# telemetry-b1.net
KiCad netlist of a schematic drawn in EAGLE
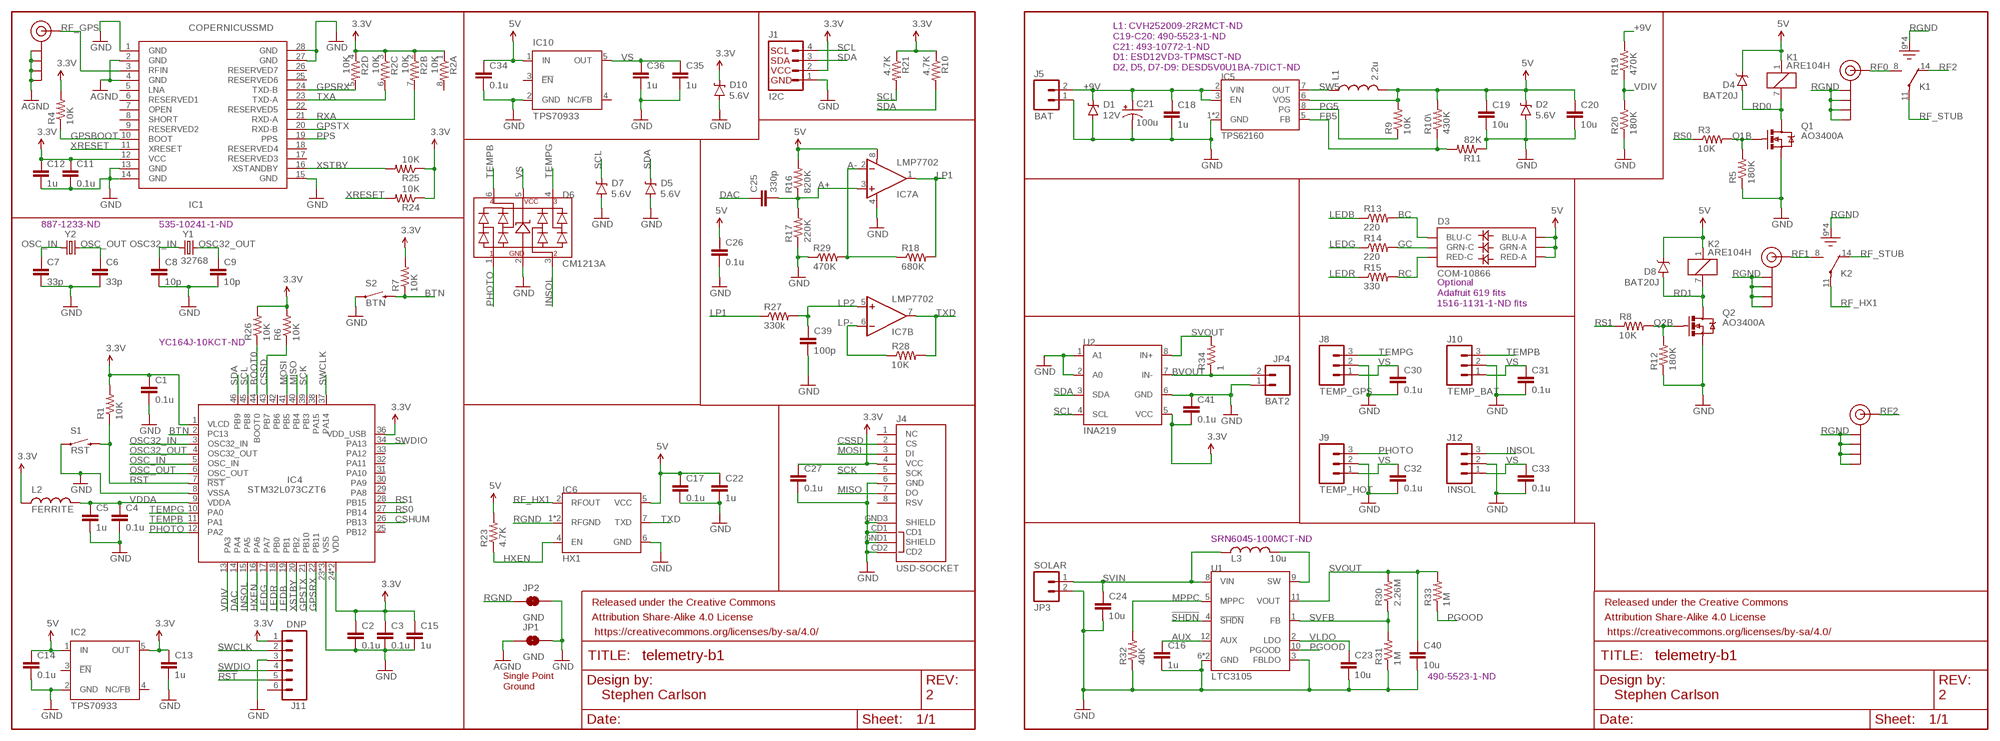
[diagram p0: schematic, sheet 1]

(export (version "E")
  (design (tool "Eeschema 10.0.6"))
  (components
    (comp (ref "C1")
      (value "0.1u")
      (footprint "eagle-import:0805")
      (libsource (lib "eagle-import") (part "CAP0805"))
    )
    (comp (ref "C2")
      (value "0.1u")
      (footprint "eagle-import:0805")
      (libsource (lib "eagle-import") (part "CAP0805"))
    )
    (comp (ref "C3")
      (value "0.1u")
      (footprint "eagle-import:0805")
      (libsource (lib "eagle-import") (part "CAP0805"))
    )
    (comp (ref "C4")
      (value "0.1u")
      (footprint "eagle-import:0805")
      (libsource (lib "eagle-import") (part "CAP0805"))
    )
    (comp (ref "C5")
      (value "1u")
      (footprint "eagle-import:0805")
      (libsource (lib "eagle-import") (part "CAP0805"))
    )
    (comp (ref "C6")
      (value "33p")
      (footprint "eagle-import:0805")
      (libsource (lib "eagle-import") (part "CAP0805"))
    )
    (comp (ref "C7")
      (value "33p")
      (footprint "eagle-import:0805")
      (libsource (lib "eagle-import") (part "CAP0805"))
    )
    (comp (ref "C8")
      (value "10p")
      (footprint "eagle-import:0805")
      (libsource (lib "eagle-import") (part "CAP0805"))
    )
    (comp (ref "C9")
      (value "10p")
      (footprint "eagle-import:0805")
      (libsource (lib "eagle-import") (part "CAP0805"))
    )
    (comp (ref "C11")
      (value "0.1u")
      (footprint "eagle-import:0805")
      (libsource (lib "eagle-import") (part "CAP0805"))
    )
    (comp (ref "C12")
      (value "1u")
      (footprint "eagle-import:0805")
      (libsource (lib "eagle-import") (part "CAP0805"))
    )
    (comp (ref "C13")
      (value "1u")
      (footprint "eagle-import:0805")
      (libsource (lib "eagle-import") (part "CAP0805"))
    )
    (comp (ref "C14")
      (value "0.1u")
      (footprint "eagle-import:0805")
      (libsource (lib "eagle-import") (part "CAP0805"))
    )
    (comp (ref "C15")
      (value "1u")
      (footprint "eagle-import:0805")
      (libsource (lib "eagle-import") (part "CAP0805"))
    )
    (comp (ref "C16")
      (value "1u")
      (footprint "eagle-import:0805")
      (libsource (lib "eagle-import") (part "CAP0805"))
    )
    (comp (ref "C17")
      (value "0.1u")
      (footprint "eagle-import:0805")
      (libsource (lib "eagle-import") (part "CAP0805"))
    )
    (comp (ref "C18")
      (value "1u")
      (footprint "eagle-import:0805")
      (libsource (lib "eagle-import") (part "CAP0805"))
    )
    (comp (ref "C19")
      (value "10u")
      (footprint "eagle-import:0805")
      (libsource (lib "eagle-import") (part "CAP0805"))
    )
    (comp (ref "C20")
      (value "10u")
      (footprint "eagle-import:0805")
      (libsource (lib "eagle-import") (part "CAP0805"))
    )
    (comp (ref "C21")
      (value "100u")
      (footprint "eagle-import:CPOL-RADIAL-10UF-25V")
      (libsource (lib "eagle-import") (part "CAP_POLPTH2"))
    )
    (comp (ref "C22")
      (value "1u")
      (footprint "eagle-import:0805")
      (libsource (lib "eagle-import") (part "CAP0805"))
    )
    (comp (ref "C23")
      (value "10u")
      (footprint "eagle-import:0805")
      (libsource (lib "eagle-import") (part "CAP0805"))
    )
    (comp (ref "C24")
      (value "10u")
      (footprint "eagle-import:0805")
      (libsource (lib "eagle-import") (part "CAP0805"))
    )
    (comp (ref "C25")
      (value "330p")
      (footprint "eagle-import:0805")
      (libsource (lib "eagle-import") (part "CAP0805"))
    )
    (comp (ref "C26")
      (value "0.1u")
      (footprint "eagle-import:0805")
      (libsource (lib "eagle-import") (part "CAP0805"))
    )
    (comp (ref "C27")
      (value "0.1u")
      (footprint "eagle-import:0805")
      (libsource (lib "eagle-import") (part "CAP0805"))
    )
    (comp (ref "C30")
      (value "0.1u")
      (footprint "eagle-import:0805")
      (libsource (lib "eagle-import") (part "CAP0805"))
    )
    (comp (ref "C31")
      (value "0.1u")
      (footprint "eagle-import:0805")
      (libsource (lib "eagle-import") (part "CAP0805"))
    )
    (comp (ref "C32")
      (value "0.1u")
      (footprint "eagle-import:0805")
      (libsource (lib "eagle-import") (part "CAP0805"))
    )
    (comp (ref "C33")
      (value "0.1u")
      (footprint "eagle-import:0805")
      (libsource (lib "eagle-import") (part "CAP0805"))
    )
    (comp (ref "C34")
      (value "0.1u")
      (footprint "eagle-import:0805")
      (libsource (lib "eagle-import") (part "CAP0805"))
    )
    (comp (ref "C35")
      (value "1u")
      (footprint "eagle-import:0805")
      (libsource (lib "eagle-import") (part "CAP0805"))
    )
    (comp (ref "C36")
      (value "1u")
      (footprint "eagle-import:0805")
      (libsource (lib "eagle-import") (part "CAP0805"))
    )
    (comp (ref "C39")
      (value "100p")
      (footprint "eagle-import:0805")
      (libsource (lib "eagle-import") (part "CAP0805"))
    )
    (comp (ref "C40")
      (value "10u")
      (footprint "eagle-import:0805")
      (libsource (lib "eagle-import") (part "CAP0805"))
    )
    (comp (ref "C41")
      (value "0.1u")
      (footprint "eagle-import:0805")
      (libsource (lib "eagle-import") (part "CAP0805"))
    )
    (comp (ref "D1")
      (value "12V")
      (footprint "eagle-import:SOD-323")
      (libsource (lib "eagle-import") (part "DIODE-ZENER5.6V"))
    )
    (comp (ref "D2")
      (value "5.6V")
      (footprint "eagle-import:SOD-323")
      (libsource (lib "eagle-import") (part "DIODE-ZENER5.6V"))
    )
    (comp (ref "D3")
      (value "COM-10866")
      (footprint "eagle-import:LED-TRICOLOR-5050")
      (libsource (lib "eagle-import") (part "LED-TRICOLOR-5050NO_IC"))
    )
    (comp (ref "D4")
      (value "BAT20J")
      (footprint "eagle-import:SOD-323")
      (libsource (lib "eagle-import") (part "DIODE-SCHOTTKY-BAT20J"))
    )
    (comp (ref "D5")
      (value "5.6V")
      (footprint "eagle-import:SOD-323")
      (libsource (lib "eagle-import") (part "DIODE-ZENER5.6V"))
    )
    (comp (ref "D6")
      (value "CM1213A")
      (footprint "eagle-import:SC70-6L")
      (libsource (lib "eagle-import") (part "CM1213A"))
    )
    (comp (ref "D7")
      (value "5.6V")
      (footprint "eagle-import:SOD-323")
      (libsource (lib "eagle-import") (part "DIODE-ZENER5.6V"))
    )
    (comp (ref "D8")
      (value "BAT20J")
      (footprint "eagle-import:SOD-323")
      (libsource (lib "eagle-import") (part "DIODE-SCHOTTKY-BAT20J"))
    )
    (comp (ref "D10")
      (value "5.6V")
      (footprint "eagle-import:SOD-323")
      (libsource (lib "eagle-import") (part "DIODE-ZENER5.6V"))
    )
    (comp (ref "FRAME1")
      (value "FRAME-LETTERNO_PACKAGE")
      (footprint "eagle-import:DUMMY")
      (fields (field (name "DESIGNER") "Nobody"))
      (libsource (lib "eagle-import") (part "FRAME-LETTERNO_PACKAGE"))
    )
    (comp (ref "FRAME2")
      (value "FRAME-LETTERNO_PACKAGE")
      (footprint "eagle-import:DUMMY")
      (fields (field (name "DESIGNER") "Nobody"))
      (libsource (lib "eagle-import") (part "FRAME-LETTERNO_PACKAGE"))
    )
    (comp (ref "IC1")
      (value "COPERNICUSSMD")
      (footprint "eagle-import:COPERNICUS")
      (libsource (lib "eagle-import") (part "COPERNICUSSMD"))
    )
    (comp (ref "IC2")
      (value "TPS70933")
      (footprint "eagle-import:SOT23-DBV")
      (fields (field (name "MF") "TEXAS INSTRUMENTS") (field (name "MPN") "TPS77033DBVT"))
      (libsource (lib "eagle-import") (part "TPS77033"))
    )
    (comp (ref "IC4")
      (value "STM32L073CZT6")
      (footprint "eagle-import:TQFP48")
      (libsource (lib "eagle-import") (part "STM32L07C"))
    )
    (comp (ref "IC5")
      (value "TPS62160")
      (footprint "eagle-import:MSOP8")
      (libsource (lib "eagle-import") (part "TPS62160"))
    )
    (comp (ref "IC6")
      (value "HX1")
      (footprint "eagle-import:HX1")
      (libsource (lib "eagle-import") (part "HX1"))
    )
    (comp (ref "IC7")
      (value "LMP7702")
      (footprint "eagle-import:SO08")
      (libsource (lib "eagle-import") (part "OPAMP-DUALU"))
    )
    (comp (ref "IC10")
      (value "TPS70933")
      (footprint "eagle-import:SOT23-DBV")
      (fields (field (name "MF") "TEXAS INSTRUMENTS") (field (name "MPN") "TPS77033DBVT"))
      (libsource (lib "eagle-import") (part "TPS77033"))
    )
    (comp (ref "J1")
      (value "I2C")
      (footprint "eagle-import:1X04_NO_SILK")
      (libsource (lib "eagle-import") (part "I2C_STANDARD_NO_SILK"))
    )
    (comp (ref "J3")
      (value "SMA_EDGE")
      (footprint "eagle-import:SMA-EDGE")
      (libsource (lib "eagle-import") (part "SMA_EDGE"))
    )
    (comp (ref "J4")
      (value "USD-SOCKET")
      (footprint "eagle-import:MICROSD_1_1")
      (libsource (lib "eagle-import") (part "USD-SOCKET"))
    )
    (comp (ref "J5")
      (value "BAT")
      (footprint "eagle-import:1X02")
      (libsource (lib "eagle-import") (part "M02PTH"))
    )
    (comp (ref "J6")
      (value "SMA_EDGE")
      (footprint "eagle-import:SMA-EDGE")
      (libsource (lib "eagle-import") (part "SMA_EDGE"))
    )
    (comp (ref "J7")
      (value "SMA_EDGE")
      (footprint "eagle-import:SMA-EDGE")
      (libsource (lib "eagle-import") (part "SMA_EDGE"))
    )
    (comp (ref "J8")
      (value "TEMP_GPS")
      (footprint "eagle-import:JST-3-PTH")
      (libsource (lib "eagle-import") (part "M03JST-PTH"))
    )
    (comp (ref "J9")
      (value "TEMP_HOT")
      (footprint "eagle-import:JST-3-PTH")
      (libsource (lib "eagle-import") (part "M03JST-PTH"))
    )
    (comp (ref "J10")
      (value "TEMP_BAT")
      (footprint "eagle-import:JST-3-PTH")
      (libsource (lib "eagle-import") (part "M03JST-PTH"))
    )
    (comp (ref "J11")
      (value "DNP")
      (footprint "eagle-import:1X06_LOCK")
      (libsource (lib "eagle-import") (part "M06LOCK"))
    )
    (comp (ref "J12")
      (value "INSOL")
      (footprint "eagle-import:JST-3-PTH")
      (libsource (lib "eagle-import") (part "M03JST-PTH"))
    )
    (comp (ref "J13")
      (value "SMA_EDGE")
      (footprint "eagle-import:SMA-EDGE")
      (libsource (lib "eagle-import") (part "SMA_EDGE"))
    )
    (comp (ref "JP1")
      (value "GND")
      (footprint "eagle-import:PAD-JUMPER-2-NC_BY_TRACE_YES_SILK")
      (libsource (lib "eagle-import") (part "JUMPER-PAD-2-NC_BY_TRACE"))
    )
    (comp (ref "JP2")
      (value "GND")
      (footprint "eagle-import:PAD-JUMPER-2-NC_BY_TRACE_YES_SILK")
      (libsource (lib "eagle-import") (part "JUMPER-PAD-2-NC_BY_TRACE"))
    )
    (comp (ref "JP3")
      (value "SOLAR")
      (footprint "eagle-import:1X02")
      (libsource (lib "eagle-import") (part "M02PTH"))
    )
    (comp (ref "JP4")
      (value "BAT2")
      (footprint "eagle-import:1X02")
      (libsource (lib "eagle-import") (part "M02PTH"))
    )
    (comp (ref "K1")
      (value "ARE104H")
      (footprint "eagle-import:RFDIL14")
      (libsource (lib "eagle-import") (part "RF_RELAY"))
    )
    (comp (ref "K2")
      (value "ARE104H")
      (footprint "eagle-import:RFDIL14")
      (libsource (lib "eagle-import") (part "RF_RELAY"))
    )
    (comp (ref "L1")
      (value "2.2u")
      (footprint "eagle-import:1008")
      (libsource (lib "eagle-import") (part "INDUCTOR1008"))
    )
    (comp (ref "L2")
      (value "FERRITE")
      (footprint "eagle-import:1206")
      (libsource (lib "eagle-import") (part "INDUCTOR1206"))
    )
    (comp (ref "L3")
      (value "10u")
      (footprint "eagle-import:SRN6045")
      (libsource (lib "eagle-import") (part "INDUCTORBOURNS_SRN6045"))
    )
    (comp (ref "Q1")
      (value "AO3400A")
      (footprint "eagle-import:SOT23-3")
      (libsource (lib "eagle-import") (part "MOSFET-NCHANNELAO3404A"))
    )
    (comp (ref "Q2")
      (value "AO3400A")
      (footprint "eagle-import:SOT23-3")
      (libsource (lib "eagle-import") (part "MOSFET-NCHANNELAO3404A"))
    )
    (comp (ref "R1")
      (value "10K")
      (footprint "eagle-import:0805")
      (libsource (lib "eagle-import") (part "RESISTOR0805-RES"))
    )
    (comp (ref "R2")
      (value "10K")
      (footprint "eagle-import:0603-ARV")
      (libsource (lib "eagle-import") (part "RESISTOR-ARRAY0603-ARV"))
    )
    (comp (ref "R3")
      (value "10K")
      (footprint "eagle-import:0805")
      (libsource (lib "eagle-import") (part "RESISTOR0805-RES"))
    )
    (comp (ref "R4")
      (value "10K")
      (footprint "eagle-import:0805")
      (libsource (lib "eagle-import") (part "RESISTOR0805-RES"))
    )
    (comp (ref "R5")
      (value "180K")
      (footprint "eagle-import:0805")
      (libsource (lib "eagle-import") (part "RESISTOR0805-RES"))
    )
    (comp (ref "R6")
      (value "10K")
      (footprint "eagle-import:0805")
      (libsource (lib "eagle-import") (part "RESISTOR0805-RES"))
    )
    (comp (ref "R7")
      (value "10K")
      (footprint "eagle-import:0805")
      (libsource (lib "eagle-import") (part "RESISTOR0805-RES"))
    )
    (comp (ref "R8")
      (value "10K")
      (footprint "eagle-import:0805")
      (libsource (lib "eagle-import") (part "RESISTOR0805-RES"))
    )
    (comp (ref "R9")
      (value "10K")
      (footprint "eagle-import:0805")
      (libsource (lib "eagle-import") (part "RESISTOR0805-RES"))
    )
    (comp (ref "R10")
      (value "4.7K")
      (footprint "eagle-import:0805")
      (libsource (lib "eagle-import") (part "RESISTOR0805-RES"))
    )
    (comp (ref "R10\\")
      (value "430K")
      (footprint "eagle-import:0805")
      (libsource (lib "eagle-import") (part "RESISTOR0805-RES"))
    )
    (comp (ref "R11")
      (value "82K")
      (footprint "eagle-import:0805")
      (libsource (lib "eagle-import") (part "RESISTOR0805-RES"))
    )
    (comp (ref "R12")
      (value "180K")
      (footprint "eagle-import:0805")
      (libsource (lib "eagle-import") (part "RESISTOR0805-RES"))
    )
    (comp (ref "R13")
      (value "220")
      (footprint "eagle-import:0805")
      (libsource (lib "eagle-import") (part "RESISTOR0805-RES"))
    )
    (comp (ref "R14")
      (value "220")
      (footprint "eagle-import:0805")
      (libsource (lib "eagle-import") (part "RESISTOR0805-RES"))
    )
    (comp (ref "R15")
      (value "330")
      (footprint "eagle-import:0805")
      (libsource (lib "eagle-import") (part "RESISTOR0805-RES"))
    )
    (comp (ref "R16")
      (value "820K")
      (footprint "eagle-import:0805")
      (libsource (lib "eagle-import") (part "RESISTOR0805-RES"))
    )
    (comp (ref "R17")
      (value "220K")
      (footprint "eagle-import:0805")
      (libsource (lib "eagle-import") (part "RESISTOR0805-RES"))
    )
    (comp (ref "R18")
      (value "680K")
      (footprint "eagle-import:0805")
      (libsource (lib "eagle-import") (part "RESISTOR0805-RES"))
    )
    (comp (ref "R19")
      (value "470K")
      (footprint "eagle-import:0805")
      (libsource (lib "eagle-import") (part "RESISTOR0805-RES"))
    )
    (comp (ref "R20")
      (value "180K")
      (footprint "eagle-import:0805")
      (libsource (lib "eagle-import") (part "RESISTOR0805-RES"))
    )
    (comp (ref "R21")
      (value "4.7K")
      (footprint "eagle-import:0805")
      (libsource (lib "eagle-import") (part "RESISTOR0805-RES"))
    )
    (comp (ref "R23")
      (value "4.7K")
      (footprint "eagle-import:0805")
      (libsource (lib "eagle-import") (part "RESISTOR0805-RES"))
    )
    (comp (ref "R24")
      (value "10K")
      (footprint "eagle-import:0805")
      (libsource (lib "eagle-import") (part "RESISTOR0805-RES"))
    )
    (comp (ref "R25")
      (value "10K")
      (footprint "eagle-import:0805")
      (libsource (lib "eagle-import") (part "RESISTOR0805-RES"))
    )
    (comp (ref "R26")
      (value "10K")
      (footprint "eagle-import:0805")
      (libsource (lib "eagle-import") (part "RESISTOR0805-RES"))
    )
    (comp (ref "R27")
      (value "330k")
      (footprint "eagle-import:0805")
      (libsource (lib "eagle-import") (part "RESISTOR0805-RES"))
    )
    (comp (ref "R28")
      (value "10K")
      (footprint "eagle-import:0805")
      (libsource (lib "eagle-import") (part "RESISTOR0805-RES"))
    )
    (comp (ref "R29")
      (value "470K")
      (footprint "eagle-import:0805")
      (libsource (lib "eagle-import") (part "RESISTOR0805-RES"))
    )
    (comp (ref "R30")
      (value "2.26M")
      (footprint "eagle-import:0805")
      (libsource (lib "eagle-import") (part "RESISTOR0805-RES"))
    )
    (comp (ref "R31")
      (value "1M")
      (footprint "eagle-import:0805")
      (libsource (lib "eagle-import") (part "RESISTOR0805-RES"))
    )
    (comp (ref "R32")
      (value "40K")
      (footprint "eagle-import:0805")
      (libsource (lib "eagle-import") (part "RESISTOR0805-RES"))
    )
    (comp (ref "R33")
      (value "1M")
      (footprint "eagle-import:0805")
      (libsource (lib "eagle-import") (part "RESISTOR0805-RES"))
    )
    (comp (ref "R34")
      (value "1")
      (footprint "eagle-import:0805")
      (libsource (lib "eagle-import") (part "RESISTOR0805-RES"))
    )
    (comp (ref "S1")
      (value "RST")
      (footprint "eagle-import:TACTILE-PTH-THIN")
      (libsource (lib "eagle-import") (part "SWITCH"))
    )
    (comp (ref "S2")
      (value "BTN")
      (footprint "eagle-import:TACTILE-PTH-THIN")
      (libsource (lib "eagle-import") (part "SWITCH"))
    )
    (comp (ref "U1")
      (value "LTC3105")
      (footprint "eagle-import:MSOP12")
      (libsource (lib "eagle-import") (part "LTC3105"))
    )
    (comp (ref "U2")
      (value "INA219")
      (footprint "eagle-import:SO8")
      (libsource (lib "eagle-import") (part "INA219"))
    )
    (comp (ref "Y1")
      (value "32768")
      (footprint "eagle-import:ABS25")
      (libsource (lib "eagle-import") (part "CRYSTAL"))
    )
    (comp (ref "Y2")
      (value "8M")
      (footprint "eagle-import:HC49UP")
      (libsource (lib "eagle-import") (part "CRYSTALSMD"))
    )
  )
  (nets
    (net (code "1") (name "/+9V") (class "Default")
      (node (ref "C18") (pin "1") (pinfunction "1_1") (pintype "passive"))
      (node (ref "C21") (pin "1") (pinfunction "+_1") (pintype "passive"))
      (node (ref "D1") (pin "C") (pinfunction "C_C") (pintype "passive"))
      (node (ref "IC5") (pin "2") (pinfunction "VIN_2") (pintype "power_in"))
      (node (ref "IC5") (pin "3") (pinfunction "EN_3") (pintype "input"))
      (node (ref "J5") (pin "2") (pinfunction "2_2") (pintype "passive"))
      (node (ref "R19") (pin "2") (pinfunction "2_2") (pintype "passive"))
    )
    (net (code "2") (name "/A+") (class "Default")
      (node (ref "C25") (pin "2") (pinfunction "2_2") (pintype "passive"))
      (node (ref "IC7") (pin "3") (pinfunction "+IN_3") (pintype "input"))
      (node (ref "R16") (pin "1") (pinfunction "1_1") (pintype "passive"))
      (node (ref "R17") (pin "2") (pinfunction "2_2") (pintype "passive"))
    )
    (net (code "3") (name "/A-") (class "Default")
      (node (ref "IC7") (pin "2") (pinfunction "-IN_2") (pintype "input"))
      (node (ref "R18") (pin "1") (pinfunction "1_1") (pintype "passive"))
      (node (ref "R29") (pin "2") (pinfunction "2_2") (pintype "passive"))
    )
    (net (code "4") (name "/AUX") (class "Default")
      (node (ref "C16") (pin "1") (pinfunction "1_1") (pintype "passive"))
      (node (ref "U1") (pin "12") (pinfunction "AUX_12") (pintype "power_in"))
    )
    (net (code "5") (name "/BC") (class "Default")
      (node (ref "D3") (pin "4") (pinfunction "BLU-C_4") (pintype "bidirectional"))
      (node (ref "R13") (pin "2") (pinfunction "2_2") (pintype "passive"))
    )
    (net (code "6") (name "/BOOT0") (class "Default")
      (node (ref "IC4") (pin "44") (pinfunction "BOOT0_44") (pintype "input"))
      (node (ref "R26") (pin "1") (pinfunction "1_1") (pintype "passive"))
    )
    (net (code "7") (name "/BTN") (class "Default")
      (node (ref "IC4") (pin "2") (pinfunction "PC13_2") (pintype "bidirectional"))
      (node (ref "R7") (pin "1") (pinfunction "1_1") (pintype "passive"))
      (node (ref "S2") (pin "2") (pinfunction "2_2") (pintype "passive"))
    )
    (net (code "8") (name "/BVOUT") (class "Default")
      (node (ref "JP4") (pin "2") (pinfunction "2_2") (pintype "passive"))
      (node (ref "R34") (pin "1") (pinfunction "1_1") (pintype "passive"))
      (node (ref "U2") (pin "7") (pinfunction "IN-_7") (pintype "passive"))
    )
    (net (code "9") (name "/CSHUM") (class "Default")
      (node (ref "IC4") (pin "26") (pinfunction "PB13_26") (pintype "bidirectional"))
    )
    (net (code "10") (name "/CSSD") (class "Default")
      (node (ref "IC4") (pin "43") (pinfunction "PB7_43") (pintype "bidirectional"))
      (node (ref "J4") (pin "2") (pinfunction "CS_2") (pintype "bidirectional"))
      (node (ref "R6") (pin "1") (pinfunction "1_1") (pintype "passive"))
    )
    (net (code "11") (name "/DAC") (class "Default")
      (node (ref "C25") (pin "1") (pinfunction "1_1") (pintype "passive"))
      (node (ref "IC4") (pin "14") (pinfunction "PA4_14") (pintype "bidirectional"))
    )
    (net (code "12") (name "/FB5") (class "Default")
      (node (ref "IC5") (pin "5") (pinfunction "FB_5") (pintype "input"))
      (node (ref "R10\\") (pin "1") (pinfunction "1_1") (pintype "passive"))
      (node (ref "R11") (pin "2") (pinfunction "2_2") (pintype "passive"))
    )
    (net (code "13") (name "/GC") (class "Default")
      (node (ref "D3") (pin "6") (pinfunction "GRN-C_6") (pintype "bidirectional"))
      (node (ref "R14") (pin "2") (pinfunction "2_2") (pintype "passive"))
    )
    (net (code "14") (name "/GPSBOOT") (class "Default")
      (node (ref "IC1") (pin "10") (pinfunction "BOOT_10") (pintype "bidirectional"))
      (node (ref "R4") (pin "1") (pinfunction "1_1") (pintype "passive"))
    )
    (net (code "15") (name "/GPSRX") (class "Default")
      (node (ref "IC1") (pin "24") (pinfunction "TXD-B_24") (pintype "bidirectional"))
      (node (ref "IC4") (pin "22") (pinfunction "PB11_22") (pintype "bidirectional"))
      (node (ref "R2") (pin "5") (pinfunction "2_5") (pintype "passive"))
    )
    (net (code "16") (name "/GPSTX") (class "Default")
      (node (ref "IC1") (pin "20") (pinfunction "RXD-B_20") (pintype "bidirectional"))
      (node (ref "IC4") (pin "21") (pinfunction "PB10_21") (pintype "bidirectional"))
    )
    (net (code "17") (name "/HXEN") (class "Default")
      (node (ref "IC4") (pin "16") (pinfunction "PA6_16") (pintype "bidirectional"))
      (node (ref "IC6") (pin "4") (pinfunction "EN_4") (pintype "input"))
      (node (ref "R23") (pin "1") (pinfunction "1_1") (pintype "passive"))
    )
    (net (code "18") (name "/INSOL") (class "Default")
      (node (ref "D6") (pin "3") (pinfunction "CH2_3") (pintype "passive"))
      (node (ref "IC4") (pin "15") (pinfunction "PA5_15") (pintype "bidirectional"))
      (node (ref "J12") (pin "3") (pinfunction "3_3") (pintype "passive"))
    )
    (net (code "19") (name "/LEDB") (class "Default")
      (node (ref "IC4") (pin "19") (pinfunction "PB1_19") (pintype "bidirectional"))
      (node (ref "R13") (pin "1") (pinfunction "1_1") (pintype "passive"))
    )
    (net (code "20") (name "/LEDG") (class "Default")
      (node (ref "IC4") (pin "17") (pinfunction "PA7_17") (pintype "bidirectional"))
      (node (ref "R14") (pin "1") (pinfunction "1_1") (pintype "passive"))
    )
    (net (code "21") (name "/LEDR") (class "Default")
      (node (ref "IC4") (pin "18") (pinfunction "PB0_18") (pintype "bidirectional"))
      (node (ref "R15") (pin "1") (pinfunction "1_1") (pintype "passive"))
    )
    (net (code "22") (name "/LP-") (class "Default")
      (node (ref "IC7") (pin "6") (pinfunction "-IN_6") (pintype "input"))
      (node (ref "R28") (pin "1") (pinfunction "1_1") (pintype "passive"))
    )
    (net (code "23") (name "/LP1") (class "Default")
      (node (ref "IC7") (pin "1") (pinfunction "OUT_1") (pintype "output"))
      (node (ref "R18") (pin "2") (pinfunction "2_2") (pintype "passive"))
      (node (ref "R27") (pin "1") (pinfunction "1_1") (pintype "passive"))
    )
    (net (code "24") (name "/LP2") (class "Default")
      (node (ref "C39") (pin "1") (pinfunction "1_1") (pintype "passive"))
      (node (ref "IC7") (pin "5") (pinfunction "+IN_5") (pintype "input"))
      (node (ref "R27") (pin "2") (pinfunction "2_2") (pintype "passive"))
    )
    (net (code "25") (name "/MISO") (class "Default")
      (node (ref "IC4") (pin "40") (pinfunction "PB4_40") (pintype "bidirectional"))
      (node (ref "J4") (pin "7") (pinfunction "DO_7") (pintype "bidirectional"))
    )
    (net (code "26") (name "/MOSI") (class "Default")
      (node (ref "IC4") (pin "41") (pinfunction "PB5_41") (pintype "bidirectional"))
      (node (ref "J4") (pin "3") (pinfunction "DI_3") (pintype "bidirectional"))
    )
    (net (code "27") (name "/MPPC") (class "Default")
      (node (ref "R32") (pin "2") (pinfunction "2_2") (pintype "passive"))
      (node (ref "U1") (pin "5") (pinfunction "MPPC_5") (pintype "input"))
    )
    (net (code "28") (name "/OSC32_IN") (class "Default")
      (node (ref "C8") (pin "1") (pinfunction "1_1") (pintype "passive"))
      (node (ref "IC4") (pin "3") (pinfunction "OSC32_IN_3") (pintype "bidirectional"))
      (node (ref "Y1") (pin "1") (pinfunction "1_1") (pintype "passive"))
    )
    (net (code "29") (name "/OSC32_OUT") (class "Default")
      (node (ref "C9") (pin "1") (pinfunction "1_1") (pintype "passive"))
      (node (ref "IC4") (pin "4") (pinfunction "OSC32_OUT_4") (pintype "bidirectional"))
      (node (ref "Y1") (pin "4") (pinfunction "2_4") (pintype "passive"))
    )
    (net (code "30") (name "/OSC_IN") (class "Default")
      (node (ref "C7") (pin "1") (pinfunction "1_1") (pintype "passive"))
      (node (ref "IC4") (pin "5") (pinfunction "OSC_IN_5") (pintype "bidirectional"))
      (node (ref "Y2") (pin "1") (pinfunction "1_1") (pintype "passive"))
    )
    (net (code "31") (name "/OSC_OUT") (class "Default")
      (node (ref "C6") (pin "1") (pinfunction "1_1") (pintype "passive"))
      (node (ref "IC4") (pin "6") (pinfunction "OSC_OUT_6") (pintype "bidirectional"))
      (node (ref "Y2") (pin "2") (pinfunction "2_2") (pintype "passive"))
    )
    (net (code "32") (name "/PG5") (class "Default")
      (node (ref "IC5") (pin "8") (pinfunction "PG_8") (pintype "open_collector"))
      (node (ref "R9") (pin "1") (pinfunction "1_1") (pintype "passive"))
    )
    (net (code "33") (name "/PGOOD") (class "Default")
      (node (ref "R33") (pin "1") (pinfunction "1_1") (pintype "passive"))
      (node (ref "U1") (pin "10") (pinfunction "PGOOD_10") (pintype "output"))
    )
    (net (code "34") (name "/PHOTO") (class "Default")
      (node (ref "D6") (pin "1") (pinfunction "CH1_1") (pintype "passive"))
      (node (ref "IC4") (pin "12") (pinfunction "PA2_12") (pintype "bidirectional"))
      (node (ref "J9") (pin "3") (pinfunction "3_3") (pintype "passive"))
    )
    (net (code "35") (name "/PPS") (class "Default")
      (node (ref "IC1") (pin "19") (pinfunction "PPS_19") (pintype "bidirectional"))
    )
    (net (code "36") (name "/Q1B") (class "Default")
      (node (ref "Q1") (pin "1") (pinfunction "G_1") (pintype "passive"))
      (node (ref "R3") (pin "2") (pinfunction "2_2") (pintype "passive"))
      (node (ref "R5") (pin "2") (pinfunction "2_2") (pintype "passive"))
    )
    (net (code "37") (name "/Q2B") (class "Default")
      (node (ref "Q2") (pin "1") (pinfunction "G_1") (pintype "passive"))
      (node (ref "R12") (pin "2") (pinfunction "2_2") (pintype "passive"))
      (node (ref "R8") (pin "2") (pinfunction "2_2") (pintype "passive"))
    )
    (net (code "38") (name "/RC") (class "Default")
      (node (ref "D3") (pin "5") (pinfunction "RED-C_5") (pintype "bidirectional"))
      (node (ref "R15") (pin "2") (pinfunction "2_2") (pintype "passive"))
    )
    (net (code "39") (name "/RD0") (class "Default")
      (node (ref "D4") (pin "A") (pinfunction "A_A") (pintype "passive"))
      (node (ref "K1") (pin "7") (pinfunction "2_7") (pintype "passive"))
      (node (ref "Q1") (pin "3") (pinfunction "D_3") (pintype "passive"))
    )
    (net (code "40") (name "/RD1") (class "Default")
      (node (ref "D8") (pin "A") (pinfunction "A_A") (pintype "passive"))
      (node (ref "K2") (pin "7") (pinfunction "2_7") (pintype "passive"))
      (node (ref "Q2") (pin "3") (pinfunction "D_3") (pintype "passive"))
    )
    (net (code "41") (name "/RF0") (class "Default")
      (node (ref "J6") (pin "SIG") (pinfunction "SIGNAL_SIG") (pintype "bidirectional"))
      (node (ref "K1") (pin "8") (pinfunction "S_8") (pintype "passive"))
    )
    (net (code "42") (name "/RF1") (class "Default")
      (node (ref "J3") (pin "SIG") (pinfunction "SIGNAL_SIG") (pintype "bidirectional"))
      (node (ref "K2") (pin "8") (pinfunction "S_8") (pintype "passive"))
    )
    (net (code "43") (name "/RF2") (class "Default")
      (node (ref "J13") (pin "SIG") (pinfunction "SIGNAL_SIG") (pintype "bidirectional"))
      (node (ref "K1") (pin "14") (pinfunction "O_14") (pintype "passive"))
    )
    (net (code "44") (name "/RF_GPS") (class "Default")
      (node (ref "IC1") (pin "3") (pinfunction "RFIN_3") (pintype "bidirectional"))
      (node (ref "J7") (pin "SIG") (pinfunction "SIGNAL_SIG") (pintype "bidirectional"))
    )
    (net (code "45") (name "/RF_HX1") (class "Default")
      (node (ref "IC6") (pin "2") (pinfunction "RFOUT_2") (pintype "output"))
      (node (ref "K2") (pin "11") (pinfunction "P_11") (pintype "passive"))
    )
    (net (code "46") (name "/RF_STUB") (class "Default")
      (node (ref "K1") (pin "11") (pinfunction "P_11") (pintype "passive"))
      (node (ref "K2") (pin "14") (pinfunction "O_14") (pintype "passive"))
    )
    (net (code "47") (name "/RGND") (class "Default")
      (node (ref "IC6") (pin "1") (pinfunction "RFGND_1") (pintype "power_in"))
      (node (ref "IC6") (pin "3") (pinfunction "RFGND_3") (pintype "power_in"))
      (node (ref "J13") (pin "GND@0") (pinfunction "GND_GND@0") (pintype "bidirectional"))
      (node (ref "J13") (pin "GND@1") (pinfunction "GND_GND@1") (pintype "bidirectional"))
      (node (ref "J13") (pin "GND@2") (pinfunction "GND_GND@2") (pintype "bidirectional"))
      (node (ref "J13") (pin "GND@3") (pinfunction "GND_GND@3") (pintype "bidirectional"))
      (node (ref "J3") (pin "GND@0") (pinfunction "GND_GND@0") (pintype "bidirectional"))
      (node (ref "J3") (pin "GND@1") (pinfunction "GND_GND@1") (pintype "bidirectional"))
      (node (ref "J3") (pin "GND@2") (pinfunction "GND_GND@2") (pintype "bidirectional"))
      (node (ref "J3") (pin "GND@3") (pinfunction "GND_GND@3") (pintype "bidirectional"))
      (node (ref "J6") (pin "GND@0") (pinfunction "GND_GND@0") (pintype "bidirectional"))
      (node (ref "J6") (pin "GND@1") (pinfunction "GND_GND@1") (pintype "bidirectional"))
      (node (ref "J6") (pin "GND@2") (pinfunction "GND_GND@2") (pintype "bidirectional"))
      (node (ref "J6") (pin "GND@3") (pinfunction "GND_GND@3") (pintype "bidirectional"))
      (node (ref "JP2") (pin "1") (pinfunction "1_1") (pintype "passive"))
      (node (ref "K1") (pin "10") (pinfunction "GND_10") (pintype "power_in"))
      (node (ref "K1") (pin "12") (pinfunction "GND_12") (pintype "power_in"))
      (node (ref "K1") (pin "13") (pinfunction "GND_13") (pintype "power_in"))
      (node (ref "K1") (pin "9") (pinfunction "GND_9") (pintype "power_in"))
      (node (ref "K2") (pin "10") (pinfunction "GND_10") (pintype "power_in"))
      (node (ref "K2") (pin "12") (pinfunction "GND_12") (pintype "power_in"))
      (node (ref "K2") (pin "13") (pinfunction "GND_13") (pintype "power_in"))
      (node (ref "K2") (pin "9") (pinfunction "GND_9") (pintype "power_in"))
    )
    (net (code "48") (name "/RS0") (class "Default")
      (node (ref "IC4") (pin "27") (pinfunction "PB14_27") (pintype "bidirectional"))
      (node (ref "R3") (pin "1") (pinfunction "1_1") (pintype "passive"))
    )
    (net (code "49") (name "/RS1") (class "Default")
      (node (ref "IC4") (pin "28") (pinfunction "PB15_28") (pintype "bidirectional"))
      (node (ref "R8") (pin "1") (pinfunction "1_1") (pintype "passive"))
    )
    (net (code "50") (name "/RXA") (class "Default")
      (node (ref "IC1") (pin "21") (pinfunction "RXD-A_21") (pintype "bidirectional"))
      (node (ref "R2") (pin "7") (pinfunction "2_7") (pintype "passive"))
    )
    (net (code "51") (name "/SCK") (class "Default")
      (node (ref "IC4") (pin "39") (pinfunction "PB3_39") (pintype "bidirectional"))
      (node (ref "J4") (pin "5") (pinfunction "SCK_5") (pintype "bidirectional"))
    )
    (net (code "52") (name "/SCL") (class "Default")
      (node (ref "D7") (pin "C") (pinfunction "C_C") (pintype "passive"))
      (node (ref "IC4") (pin "45") (pinfunction "PB8_45") (pintype "bidirectional"))
      (node (ref "J1") (pin "4") (pinfunction "4_4") (pintype "passive"))
      (node (ref "R21") (pin "2") (pinfunction "2_2") (pintype "passive"))
      (node (ref "U2") (pin "4") (pinfunction "SCL_4") (pintype "bidirectional"))
    )
    (net (code "53") (name "/SDA") (class "Default")
      (node (ref "D5") (pin "C") (pinfunction "C_C") (pintype "passive"))
      (node (ref "IC4") (pin "46") (pinfunction "PB9_46") (pintype "bidirectional"))
      (node (ref "J1") (pin "3") (pinfunction "3_3") (pintype "passive"))
      (node (ref "R10") (pin "2") (pinfunction "2_2") (pintype "passive"))
      (node (ref "U2") (pin "3") (pinfunction "SDA_3") (pintype "bidirectional"))
    )
    (net (code "54") (name "/SVFB") (class "Default")
      (node (ref "R30") (pin "1") (pinfunction "1_1") (pintype "passive"))
      (node (ref "R31") (pin "2") (pinfunction "2_2") (pintype "passive"))
      (node (ref "U1") (pin "1") (pinfunction "FB_1") (pintype "input"))
    )
    (net (code "55") (name "/SVIN") (class "Default")
      (node (ref "C24") (pin "1") (pinfunction "1_1") (pintype "passive"))
      (node (ref "JP3") (pin "1") (pinfunction "1_1") (pintype "passive"))
      (node (ref "L3") (pin "1") (pinfunction "1_1") (pintype "passive"))
      (node (ref "U1") (pin "8") (pinfunction "VIN_8") (pintype "power_in"))
    )
    (net (code "56") (name "/SVOUT") (class "Default")
      (node (ref "C40") (pin "1") (pinfunction "1_1") (pintype "passive"))
      (node (ref "R30") (pin "2") (pinfunction "2_2") (pintype "passive"))
      (node (ref "R33") (pin "2") (pinfunction "2_2") (pintype "passive"))
      (node (ref "R34") (pin "2") (pinfunction "2_2") (pintype "passive"))
      (node (ref "U1") (pin "11") (pinfunction "VOUT_11") (pintype "power_in"))
      (node (ref "U2") (pin "8") (pinfunction "IN+_8") (pintype "passive"))
    )
    (net (code "57") (name "/SW5") (class "Default")
      (node (ref "IC5") (pin "7") (pinfunction "OUT_7") (pintype "output"))
      (node (ref "L1") (pin "1") (pinfunction "1_1") (pintype "passive"))
    )
    (net (code "58") (name "/SWCLK") (class "Default")
      (node (ref "IC4") (pin "37") (pinfunction "PA14_37") (pintype "bidirectional"))
      (node (ref "J11") (pin "2") (pinfunction "2_2") (pintype "passive"))
    )
    (net (code "59") (name "/SWDIO") (class "Default")
      (node (ref "IC4") (pin "34") (pinfunction "PA13_34") (pintype "bidirectional"))
      (node (ref "J11") (pin "4") (pinfunction "4_4") (pintype "passive"))
    )
    (net (code "60") (name "/TEMPB") (class "Default")
      (node (ref "D6") (pin "6") (pinfunction "CH4_6") (pintype "passive"))
      (node (ref "IC4") (pin "11") (pinfunction "PA1_11") (pintype "bidirectional"))
      (node (ref "J10") (pin "3") (pinfunction "3_3") (pintype "passive"))
    )
    (net (code "61") (name "/TEMPG") (class "Default")
      (node (ref "D6") (pin "4") (pinfunction "CH3_4") (pintype "passive"))
      (node (ref "IC4") (pin "10") (pinfunction "PA0_10") (pintype "bidirectional"))
      (node (ref "J8") (pin "3") (pinfunction "3_3") (pintype "passive"))
    )
    (net (code "62") (name "/TXA") (class "Default")
      (node (ref "IC1") (pin "23") (pinfunction "TXD-A_23") (pintype "bidirectional"))
      (node (ref "R2") (pin "6") (pinfunction "2_6") (pintype "passive"))
    )
    (net (code "63") (name "/TXD") (class "Default")
      (node (ref "IC6") (pin "7") (pinfunction "TXD_7") (pintype "input"))
      (node (ref "IC7") (pin "7") (pinfunction "OUT_7") (pintype "output"))
      (node (ref "R28") (pin "2") (pinfunction "2_2") (pintype "passive"))
    )
    (net (code "64") (name "/VDDA") (class "Default")
      (node (ref "C4") (pin "1") (pinfunction "1_1") (pintype "passive"))
      (node (ref "C5") (pin "1") (pinfunction "1_1") (pintype "passive"))
      (node (ref "IC4") (pin "9") (pinfunction "VDDA_9") (pintype "power_in"))
      (node (ref "L2") (pin "2") (pinfunction "2_2") (pintype "passive"))
    )
    (net (code "65") (name "/VDIV") (class "Default")
      (node (ref "IC4") (pin "13") (pinfunction "PA3_13") (pintype "bidirectional"))
      (node (ref "R19") (pin "1") (pinfunction "1_1") (pintype "passive"))
      (node (ref "R20") (pin "2") (pinfunction "2_2") (pintype "passive"))
    )
    (net (code "66") (name "/VLDO") (class "Default")
      (node (ref "C23") (pin "1") (pinfunction "1_1") (pintype "passive"))
      (node (ref "U1") (pin "2") (pinfunction "LDO_2") (pintype "power_in"))
    )
    (net (code "67") (name "/VS") (class "Default")
      (node (ref "C30") (pin "1") (pinfunction "1_1") (pintype "passive"))
      (node (ref "C31") (pin "1") (pinfunction "1_1") (pintype "passive"))
      (node (ref "C32") (pin "1") (pinfunction "1_1") (pintype "passive"))
      (node (ref "C33") (pin "1") (pinfunction "1_1") (pintype "passive"))
      (node (ref "C35") (pin "1") (pinfunction "1_1") (pintype "passive"))
      (node (ref "C36") (pin "1") (pinfunction "1_1") (pintype "passive"))
      (node (ref "D6") (pin "5") (pinfunction "VCC_5") (pintype "power_in"))
      (node (ref "IC10") (pin "5") (pinfunction "OUT_5") (pintype "passive"))
      (node (ref "J10") (pin "1") (pinfunction "1_1") (pintype "passive"))
      (node (ref "J12") (pin "1") (pinfunction "1_1") (pintype "passive"))
      (node (ref "J8") (pin "1") (pinfunction "1_1") (pintype "passive"))
      (node (ref "J9") (pin "1") (pinfunction "1_1") (pintype "passive"))
    )
    (net (code "68") (name "/XRESET") (class "Default")
      (node (ref "IC1") (pin "11") (pinfunction "XRESET_11") (pintype "bidirectional"))
      (node (ref "R24") (pin "2") (pinfunction "2_2") (pintype "passive"))
    )
    (net (code "69") (name "/XSTBY") (class "Default")
      (node (ref "IC1") (pin "16") (pinfunction "XSTANDBY_16") (pintype "bidirectional"))
      (node (ref "IC4") (pin "20") (pinfunction "PB2_20") (pintype "bidirectional"))
      (node (ref "R25") (pin "2") (pinfunction "2_2") (pintype "passive"))
    )
    (net (code "70") (name "/~{RST}") (class "Default")
      (node (ref "IC4") (pin "7") (pinfunction "~{RST}_7") (pintype "input"))
      (node (ref "J11") (pin "5") (pinfunction "5_5") (pintype "passive"))
      (node (ref "R1") (pin "1") (pinfunction "1_1") (pintype "passive"))
      (node (ref "S1") (pin "2") (pinfunction "2_2") (pintype "passive"))
    )
    (net (code "71") (name "/~{SHDN}") (class "Default")
      (node (ref "U1") (pin "4") (pinfunction "~{SHDN}_4") (pintype "passive"))
    )
    (net (code "72") (name "3.3V") (class "Default")
      (node (ref "C1") (pin "1") (pinfunction "1_1") (pintype "passive"))
      (node (ref "C11") (pin "1") (pinfunction "1_1") (pintype "passive"))
      (node (ref "C12") (pin "1") (pinfunction "1_1") (pintype "passive"))
      (node (ref "C13") (pin "1") (pinfunction "1_1") (pintype "passive"))
      (node (ref "C15") (pin "1") (pinfunction "1_1") (pintype "passive"))
      (node (ref "C2") (pin "1") (pinfunction "1_1") (pintype "passive"))
      (node (ref "C27") (pin "1") (pinfunction "1_1") (pintype "passive"))
      (node (ref "C3") (pin "1") (pinfunction "1_1") (pintype "passive"))
      (node (ref "C41") (pin "2") (pinfunction "2_2") (pintype "passive"))
      (node (ref "D10") (pin "C") (pinfunction "C_C") (pintype "passive"))
      (node (ref "IC1") (pin "12") (pinfunction "VCC_12") (pintype "bidirectional"))
      (node (ref "IC2") (pin "5") (pinfunction "OUT_5") (pintype "passive"))
      (node (ref "IC4") (pin "1") (pinfunction "VLCD_1") (pintype "power_in"))
      (node (ref "IC4") (pin "24") (pinfunction "VDD_24") (pintype "power_in"))
      (node (ref "IC4") (pin "36") (pinfunction "VDD_USB_36") (pintype "power_in"))
      (node (ref "IC4") (pin "48") (pinfunction "VDD_48") (pintype "power_in"))
      (node (ref "J1") (pin "2") (pinfunction "2_2") (pintype "passive"))
      (node (ref "J11") (pin "1") (pinfunction "1_1") (pintype "passive"))
      (node (ref "J4") (pin "4") (pinfunction "VCC_4") (pintype "bidirectional"))
      (node (ref "L2") (pin "1") (pinfunction "1_1") (pintype "passive"))
      (node (ref "R1") (pin "2") (pinfunction "2_2") (pintype "passive"))
      (node (ref "R10") (pin "1") (pinfunction "1_1") (pintype "passive"))
      (node (ref "R2") (pin "1") (pinfunction "1_1") (pintype "passive"))
      (node (ref "R2") (pin "2") (pinfunction "1_2") (pintype "passive"))
      (node (ref "R2") (pin "3") (pinfunction "1_3") (pintype "passive"))
      (node (ref "R2") (pin "4") (pinfunction "1_4") (pintype "passive"))
      (node (ref "R21") (pin "1") (pinfunction "1_1") (pintype "passive"))
      (node (ref "R24") (pin "1") (pinfunction "1_1") (pintype "passive"))
      (node (ref "R25") (pin "1") (pinfunction "1_1") (pintype "passive"))
      (node (ref "R26") (pin "2") (pinfunction "2_2") (pintype "passive"))
      (node (ref "R4") (pin "2") (pinfunction "2_2") (pintype "passive"))
      (node (ref "R6") (pin "2") (pinfunction "2_2") (pintype "passive"))
      (node (ref "R7") (pin "2") (pinfunction "2_2") (pintype "passive"))
      (node (ref "U2") (pin "5") (pinfunction "VCC_5") (pintype "power_in"))
    )
    (net (code "73") (name "5V") (class "Default")
      (node (ref "C14") (pin "1") (pinfunction "1_1") (pintype "passive"))
      (node (ref "C17") (pin "1") (pinfunction "1_1") (pintype "passive"))
      (node (ref "C19") (pin "1") (pinfunction "1_1") (pintype "passive"))
      (node (ref "C20") (pin "1") (pinfunction "1_1") (pintype "passive"))
      (node (ref "C22") (pin "1") (pinfunction "1_1") (pintype "passive"))
      (node (ref "C26") (pin "1") (pinfunction "1_1") (pintype "passive"))
      (node (ref "C34") (pin "1") (pinfunction "1_1") (pintype "passive"))
      (node (ref "D2") (pin "C") (pinfunction "C_C") (pintype "passive"))
      (node (ref "D3") (pin "1") (pinfunction "GRN-A_1") (pintype "bidirectional"))
      (node (ref "D3") (pin "2") (pinfunction "RED-A_2") (pintype "bidirectional"))
      (node (ref "D3") (pin "3") (pinfunction "BLU-A_3") (pintype "bidirectional"))
      (node (ref "D4") (pin "C") (pinfunction "C_C") (pintype "passive"))
      (node (ref "D8") (pin "C") (pinfunction "C_C") (pintype "passive"))
      (node (ref "IC10") (pin "1") (pinfunction "IN_1") (pintype "input"))
      (node (ref "IC2") (pin "1") (pinfunction "IN_1") (pintype "input"))
      (node (ref "IC5") (pin "6") (pinfunction "VOS_6") (pintype "input"))
      (node (ref "IC6") (pin "5") (pinfunction "VCC_5") (pintype "power_in"))
      (node (ref "IC7") (pin "8") (pinfunction "V+_8") (pintype "power_in"))
      (node (ref "K1") (pin "1") (pinfunction "1_1") (pintype "passive"))
      (node (ref "K2") (pin "1") (pinfunction "1_1") (pintype "passive"))
      (node (ref "L1") (pin "2") (pinfunction "2_2") (pintype "passive"))
      (node (ref "R10\\") (pin "2") (pinfunction "2_2") (pintype "passive"))
      (node (ref "R16") (pin "2") (pinfunction "2_2") (pintype "passive"))
      (node (ref "R23") (pin "2") (pinfunction "2_2") (pintype "passive"))
      (node (ref "R9") (pin "2") (pinfunction "2_2") (pintype "passive"))
    )
    (net (code "74") (name "AGND") (class "Default")
      (node (ref "IC1") (pin "2") (pinfunction "GND_2") (pintype "bidirectional"))
      (node (ref "IC1") (pin "4") (pinfunction "GND_4") (pintype "bidirectional"))
      (node (ref "J7") (pin "GND@0") (pinfunction "GND_GND@0") (pintype "bidirectional"))
      (node (ref "J7") (pin "GND@1") (pinfunction "GND_GND@1") (pintype "bidirectional"))
      (node (ref "J7") (pin "GND@2") (pinfunction "GND_GND@2") (pintype "bidirectional"))
      (node (ref "J7") (pin "GND@3") (pinfunction "GND_GND@3") (pintype "bidirectional"))
      (node (ref "JP1") (pin "1") (pinfunction "1_1") (pintype "passive"))
    )
    (net (code "75") (name "GND") (class "Default")
      (node (ref "C1") (pin "2") (pinfunction "2_2") (pintype "passive"))
      (node (ref "C11") (pin "2") (pinfunction "2_2") (pintype "passive"))
      (node (ref "C12") (pin "2") (pinfunction "2_2") (pintype "passive"))
      (node (ref "C13") (pin "2") (pinfunction "2_2") (pintype "passive"))
      (node (ref "C14") (pin "2") (pinfunction "2_2") (pintype "passive"))
      (node (ref "C15") (pin "2") (pinfunction "2_2") (pintype "passive"))
      (node (ref "C16") (pin "2") (pinfunction "2_2") (pintype "passive"))
      (node (ref "C17") (pin "2") (pinfunction "2_2") (pintype "passive"))
      (node (ref "C18") (pin "2") (pinfunction "2_2") (pintype "passive"))
      (node (ref "C19") (pin "2") (pinfunction "2_2") (pintype "passive"))
      (node (ref "C2") (pin "2") (pinfunction "2_2") (pintype "passive"))
      (node (ref "C20") (pin "2") (pinfunction "2_2") (pintype "passive"))
      (node (ref "C21") (pin "2") (pinfunction "-_2") (pintype "passive"))
      (node (ref "C22") (pin "2") (pinfunction "2_2") (pintype "passive"))
      (node (ref "C23") (pin "2") (pinfunction "2_2") (pintype "passive"))
      (node (ref "C24") (pin "2") (pinfunction "2_2") (pintype "passive"))
      (node (ref "C26") (pin "2") (pinfunction "2_2") (pintype "passive"))
      (node (ref "C27") (pin "2") (pinfunction "2_2") (pintype "passive"))
      (node (ref "C3") (pin "2") (pinfunction "2_2") (pintype "passive"))
      (node (ref "C30") (pin "2") (pinfunction "2_2") (pintype "passive"))
      (node (ref "C31") (pin "2") (pinfunction "2_2") (pintype "passive"))
      (node (ref "C32") (pin "2") (pinfunction "2_2") (pintype "passive"))
      (node (ref "C33") (pin "2") (pinfunction "2_2") (pintype "passive"))
      (node (ref "C34") (pin "2") (pinfunction "2_2") (pintype "passive"))
      (node (ref "C35") (pin "2") (pinfunction "2_2") (pintype "passive"))
      (node (ref "C36") (pin "2") (pinfunction "2_2") (pintype "passive"))
      (node (ref "C39") (pin "2") (pinfunction "2_2") (pintype "passive"))
      (node (ref "C4") (pin "2") (pinfunction "2_2") (pintype "passive"))
      (node (ref "C40") (pin "2") (pinfunction "2_2") (pintype "passive"))
      (node (ref "C41") (pin "1") (pinfunction "1_1") (pintype "passive"))
      (node (ref "C5") (pin "2") (pinfunction "2_2") (pintype "passive"))
      (node (ref "C6") (pin "2") (pinfunction "2_2") (pintype "passive"))
      (node (ref "C7") (pin "2") (pinfunction "2_2") (pintype "passive"))
      (node (ref "C8") (pin "2") (pinfunction "2_2") (pintype "passive"))
      (node (ref "C9") (pin "2") (pinfunction "2_2") (pintype "passive"))
      (node (ref "D1") (pin "A") (pinfunction "A_A") (pintype "passive"))
      (node (ref "D10") (pin "A") (pinfunction "A_A") (pintype "passive"))
      (node (ref "D2") (pin "A") (pinfunction "A_A") (pintype "passive"))
      (node (ref "D5") (pin "A") (pinfunction "A_A") (pintype "passive"))
      (node (ref "D6") (pin "2") (pinfunction "GND_2") (pintype "power_in"))
      (node (ref "D7") (pin "A") (pinfunction "A_A") (pintype "passive"))
      (node (ref "IC1") (pin "1") (pinfunction "GND_1") (pintype "bidirectional"))
      (node (ref "IC1") (pin "13") (pinfunction "GND_13") (pintype "bidirectional"))
      (node (ref "IC1") (pin "14") (pinfunction "GND_14") (pintype "bidirectional"))
      (node (ref "IC1") (pin "15") (pinfunction "GND_15") (pintype "bidirectional"))
      (node (ref "IC1") (pin "27") (pinfunction "GND_27") (pintype "bidirectional"))
      (node (ref "IC1") (pin "28") (pinfunction "GND_28") (pintype "bidirectional"))
      (node (ref "IC10") (pin "2") (pinfunction "GND_2") (pintype "power_in"))
      (node (ref "IC2") (pin "2") (pinfunction "GND_2") (pintype "power_in"))
      (node (ref "IC4") (pin "23") (pinfunction "VSS_23") (pintype "power_in"))
      (node (ref "IC4") (pin "35") (pinfunction "VSS_35") (pintype "power_in"))
      (node (ref "IC4") (pin "47") (pinfunction "VSS_47") (pintype "power_in"))
      (node (ref "IC4") (pin "8") (pinfunction "VSSA_8") (pintype "power_in"))
      (node (ref "IC5") (pin "1") (pinfunction "GND_1") (pintype "power_in"))
      (node (ref "IC5") (pin "4") (pinfunction "GND_4") (pintype "power_in"))
      (node (ref "IC6") (pin "6") (pinfunction "GND_6") (pintype "power_in"))
      (node (ref "IC7") (pin "4") (pinfunction "V-_4") (pintype "power_in"))
      (node (ref "J1") (pin "1") (pinfunction "1_1") (pintype "passive"))
      (node (ref "J10") (pin "2") (pinfunction "2_2") (pintype "passive"))
      (node (ref "J11") (pin "3") (pinfunction "3_3") (pintype "passive"))
      (node (ref "J12") (pin "2") (pinfunction "2_2") (pintype "passive"))
      (node (ref "J4") (pin "6") (pinfunction "GND_6") (pintype "bidirectional"))
      (node (ref "J4") (pin "CD1") (pinfunction "CD1_CD1") (pintype "bidirectional"))
      (node (ref "J4") (pin "CD2") (pinfunction "CD2_CD2") (pintype "bidirectional"))
      (node (ref "J4") (pin "GND1") (pinfunction "SHIELD_GND1") (pintype "bidirectional"))
      (node (ref "J4") (pin "GND3") (pinfunction "SHIELD_GND3") (pintype "bidirectional"))
      (node (ref "J5") (pin "1") (pinfunction "1_1") (pintype "passive"))
      (node (ref "J8") (pin "2") (pinfunction "2_2") (pintype "passive"))
      (node (ref "J9") (pin "2") (pinfunction "2_2") (pintype "passive"))
      (node (ref "JP1") (pin "2") (pinfunction "2_2") (pintype "passive"))
      (node (ref "JP2") (pin "2") (pinfunction "2_2") (pintype "passive"))
      (node (ref "JP3") (pin "2") (pinfunction "2_2") (pintype "passive"))
      (node (ref "JP4") (pin "1") (pinfunction "1_1") (pintype "passive"))
      (node (ref "Q1") (pin "2") (pinfunction "S_2") (pintype "passive"))
      (node (ref "Q2") (pin "2") (pinfunction "S_2") (pintype "passive"))
      (node (ref "R11") (pin "1") (pinfunction "1_1") (pintype "passive"))
      (node (ref "R12") (pin "1") (pinfunction "1_1") (pintype "passive"))
      (node (ref "R17") (pin "1") (pinfunction "1_1") (pintype "passive"))
      (node (ref "R20") (pin "1") (pinfunction "1_1") (pintype "passive"))
      (node (ref "R29") (pin "1") (pinfunction "1_1") (pintype "passive"))
      (node (ref "R31") (pin "1") (pinfunction "1_1") (pintype "passive"))
      (node (ref "R32") (pin "1") (pinfunction "1_1") (pintype "passive"))
      (node (ref "R5") (pin "1") (pinfunction "1_1") (pintype "passive"))
      (node (ref "S1") (pin "1") (pinfunction "1_1") (pintype "passive"))
      (node (ref "S2") (pin "1") (pinfunction "1_1") (pintype "passive"))
      (node (ref "U1") (pin "3") (pinfunction "FBLDO_3") (pintype "input"))
      (node (ref "U1") (pin "6") (pinfunction "GND_6") (pintype "power_in"))
      (node (ref "U1") (pin "7") (pinfunction "GND_7") (pintype "power_in"))
      (node (ref "U2") (pin "1") (pinfunction "A1_1") (pintype "input"))
      (node (ref "U2") (pin "2") (pinfunction "A0_2") (pintype "input"))
      (node (ref "U2") (pin "6") (pinfunction "GND_6") (pintype "power_in"))
    )
    (net (code "76") (name "Net-(U1-SW)") (class "Default")
      (node (ref "L3") (pin "2") (pinfunction "2_2") (pintype "passive"))
      (node (ref "U1") (pin "9") (pinfunction "SW_9") (pintype "passive"))
    )
    (net (code "77") (name "unconnected-(IC1-LNA-Pad5)") (class "Default")
      (node (ref "IC1") (pin "5") (pinfunction "LNA_5") (pintype "bidirectional"))
    )
    (net (code "78") (name "unconnected-(IC1-OPEN-Pad7)") (class "Default")
      (node (ref "IC1") (pin "7") (pinfunction "OPEN_7") (pintype "bidirectional"))
    )
    (net (code "79") (name "unconnected-(IC1-RESERVED1-Pad6)") (class "Default")
      (node (ref "IC1") (pin "6") (pinfunction "RESERVED1_6") (pintype "bidirectional"))
    )
    (net (code "80") (name "unconnected-(IC1-RESERVED2-Pad9)") (class "Default")
      (node (ref "IC1") (pin "9") (pinfunction "RESERVED2_9") (pintype "bidirectional"))
    )
    (net (code "81") (name "unconnected-(IC1-RESERVED3-Pad17)") (class "Default")
      (node (ref "IC1") (pin "17") (pinfunction "RESERVED3_17") (pintype "bidirectional"))
    )
    (net (code "82") (name "unconnected-(IC1-RESERVED4-Pad18)") (class "Default")
      (node (ref "IC1") (pin "18") (pinfunction "RESERVED4_18") (pintype "bidirectional"))
    )
    (net (code "83") (name "unconnected-(IC1-RESERVED5-Pad22)") (class "Default")
      (node (ref "IC1") (pin "22") (pinfunction "RESERVED5_22") (pintype "bidirectional"))
    )
    (net (code "84") (name "unconnected-(IC1-RESERVED6-Pad25)") (class "Default")
      (node (ref "IC1") (pin "25") (pinfunction "RESERVED6_25") (pintype "bidirectional"))
    )
    (net (code "85") (name "unconnected-(IC1-RESERVED7-Pad26)") (class "Default")
      (node (ref "IC1") (pin "26") (pinfunction "RESERVED7_26") (pintype "bidirectional"))
    )
    (net (code "86") (name "unconnected-(IC1-SHORT-Pad8)") (class "Default")
      (node (ref "IC1") (pin "8") (pinfunction "SHORT_8") (pintype "bidirectional"))
    )
    (net (code "87") (name "unconnected-(IC2-NC{slash}FB-Pad4)") (class "Default")
      (node (ref "IC2") (pin "4") (pinfunction "NC/FB_4") (pintype "passive"))
    )
    (net (code "88") (name "unconnected-(IC2-~{EN}-Pad3)") (class "Default")
      (node (ref "IC2") (pin "3") (pinfunction "~{EN}_3") (pintype "input"))
    )
    (net (code "89") (name "unconnected-(IC4-PA8-Pad29)") (class "Default")
      (node (ref "IC4") (pin "29") (pinfunction "PA8_29") (pintype "bidirectional"))
    )
    (net (code "90") (name "unconnected-(IC4-PA9-Pad30)") (class "Default")
      (node (ref "IC4") (pin "30") (pinfunction "PA9_30") (pintype "bidirectional"))
    )
    (net (code "91") (name "unconnected-(IC4-PA10-Pad31)") (class "Default")
      (node (ref "IC4") (pin "31") (pinfunction "PA10_31") (pintype "bidirectional"))
    )
    (net (code "92") (name "unconnected-(IC4-PA11-Pad32)") (class "Default")
      (node (ref "IC4") (pin "32") (pinfunction "PA11_32") (pintype "bidirectional"))
    )
    (net (code "93") (name "unconnected-(IC4-PA12-Pad33)") (class "Default")
      (node (ref "IC4") (pin "33") (pinfunction "PA12_33") (pintype "bidirectional"))
    )
    (net (code "94") (name "unconnected-(IC4-PA15-Pad38)") (class "Default")
      (node (ref "IC4") (pin "38") (pinfunction "PA15_38") (pintype "bidirectional"))
    )
    (net (code "95") (name "unconnected-(IC4-PB6-Pad42)") (class "Default")
      (node (ref "IC4") (pin "42") (pinfunction "PB6_42") (pintype "bidirectional"))
    )
    (net (code "96") (name "unconnected-(IC4-PB12-Pad25)") (class "Default")
      (node (ref "IC4") (pin "25") (pinfunction "PB12_25") (pintype "bidirectional"))
    )
    (net (code "97") (name "unconnected-(IC10-NC{slash}FB-Pad4)") (class "Default")
      (node (ref "IC10") (pin "4") (pinfunction "NC/FB_4") (pintype "passive"))
    )
    (net (code "98") (name "unconnected-(IC10-~{EN}-Pad3)") (class "Default")
      (node (ref "IC10") (pin "3") (pinfunction "~{EN}_3") (pintype "input"))
    )
    (net (code "99") (name "unconnected-(J4-NC-Pad1)") (class "Default")
      (node (ref "J4") (pin "1") (pinfunction "NC_1") (pintype "bidirectional"))
    )
    (net (code "100") (name "unconnected-(J4-RSV-Pad8)") (class "Default")
      (node (ref "J4") (pin "8") (pinfunction "RSV_8") (pintype "bidirectional"))
    )
    (net (code "101") (name "unconnected-(J11-Pad6)") (class "Default")
      (node (ref "J11") (pin "6") (pinfunction "6_6") (pintype "passive"))
    )
    (net (code "102") (name "unconnected-(R2A-2-Pad8)") (class "Default")
      (node (ref "R2") (pin "8") (pinfunction "2_8") (pintype "passive"))
    )
  )
)
